# main.net
KiCad netlist of a schematic drawn in Altium Designer
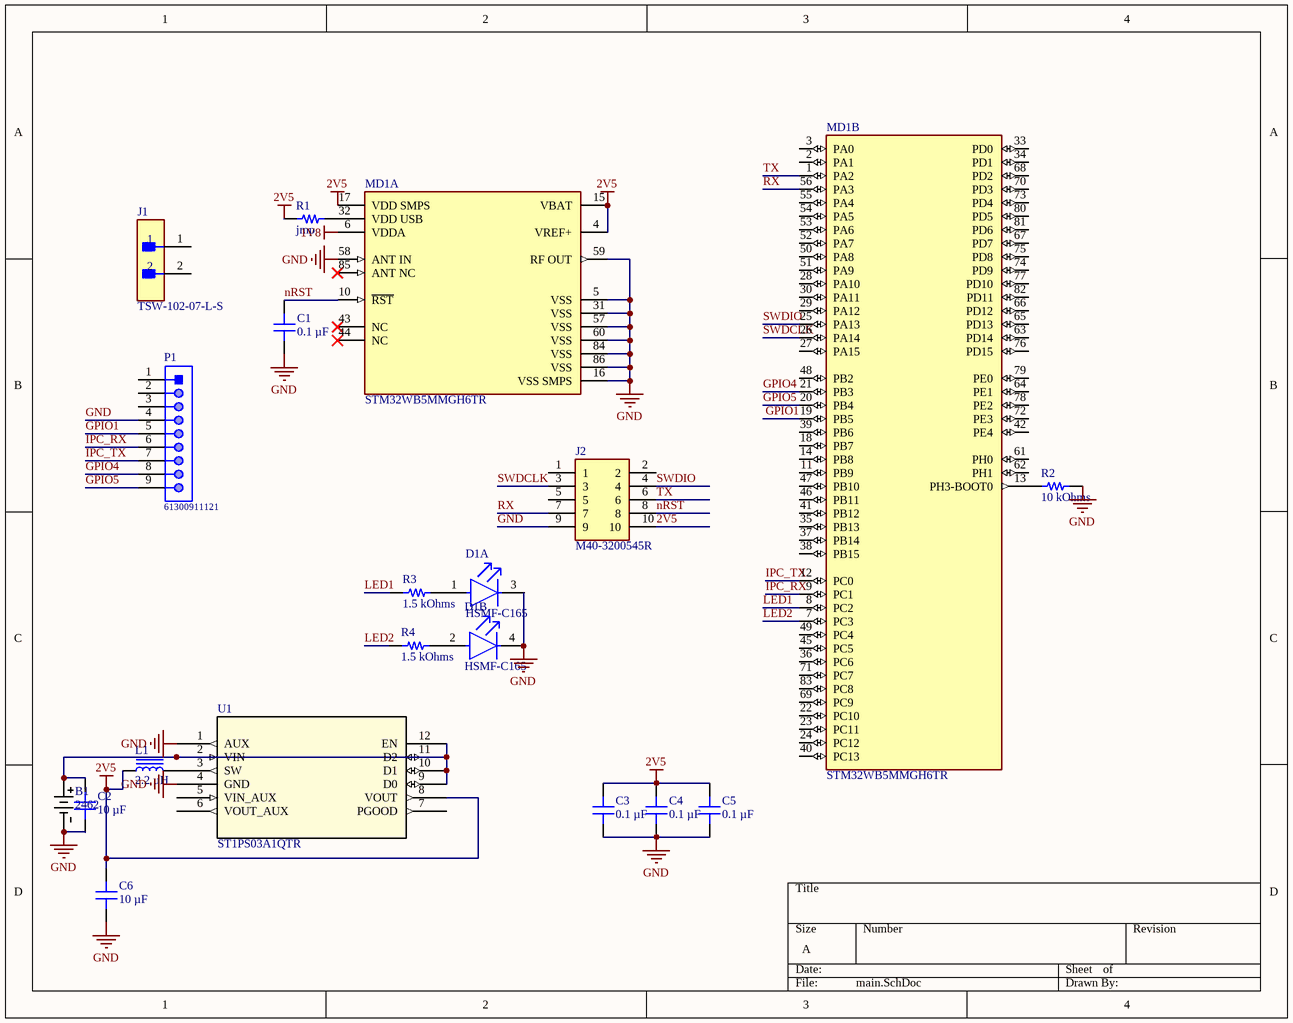
[diagram p0: main.SchDoc]

(export (version "E")
  (design (tool "Eeschema 10.0.6"))
  (components
    (comp (ref "B1")
      (value "2462")
      (footprint "2462_KEY")
      (description "No Description Available")
      (libsource (lib "2462") (part "2462"))
    )
    (comp (ref "C1")
      (value "0.1 µF")
      (footprint "CAP 0402_1005")
      (description "CAP CER 0.1UF 4V X5R 0402")
      (fields (field (name "PART NUMBER") "C0402C104K7PAC7867") (field (name "MANUFACTURER") "KEMET"))
      (libsource (lib "Celestial Altium Library - altium_library") (part "Capacitor"))
    )
    (comp (ref "C2")
      (value "10 µF")
      (footprint "CAP 0603_1608")
      (description "CAP CER 10UF 6.3V X5R 0603")
      (fields
        (field (name "PART NUMBER") "GRM188R60J106ME47D")
        (field (name "MANUFACTURER") "Murata Electronics")
      )
      (libsource (lib "Celestial Altium Library - altium_library") (part "Capacitor"))
    )
    (comp (ref "C3")
      (value "0.1 µF")
      (footprint "CAP 0402_1005")
      (description "CAP CER 0402 0.1UF 16V X7R 10%")
      (fields (field (name "PART NUMBER") "C0402C104K4RECAUTO") (field (name "MANUFACTURER") "KEMET"))
      (libsource (lib "Celestial Altium Library - altium_library") (part "Capacitor"))
    )
    (comp (ref "C4")
      (value "0.1 µF")
      (footprint "CAP 0402_1005")
      (description "CAP CER 0.1UF 4V X5R 0402")
      (fields (field (name "PART NUMBER") "C0402C104K7PAC7867") (field (name "MANUFACTURER") "KEMET"))
      (libsource (lib "Celestial Altium Library - altium_library") (part "Capacitor"))
    )
    (comp (ref "C5")
      (value "0.1 µF")
      (footprint "CAP 0402_1005")
      (description "CAP CER 0.1UF 4V X5R 0402")
      (fields (field (name "PART NUMBER") "C0402C104K7PAC7867") (field (name "MANUFACTURER") "KEMET"))
      (libsource (lib "Celestial Altium Library - altium_library") (part "Capacitor"))
    )
    (comp (ref "C6")
      (value "10 µF")
      (footprint "CAP 0603_1608")
      (description "CAP CER 10UF 6.3V X5R 0603")
      (fields
        (field (name "PART NUMBER") "GRM188R60J106ME47D")
        (field (name "MANUFACTURER") "Murata Electronics")
      )
      (libsource (lib "Celestial Altium Library - altium_library") (part "Capacitor"))
    )
    (comp (ref "D1")
      (value "HSMF-C165")
      (footprint "FP-HSMF-C165-MFG")
      (description "LED GREEN/RED DIFFUSED 0603 SMD")
      (libsource (lib "Altium Content Vault") (part "7c1fe340d8ce6b5db8c50b7ec3493de"))
    )
    (comp (ref "J1")
      (value "TSW-102-07-L-S")
      (footprint "FP-TSW-102-07-L-S-MFG")
      (description "CONN HEADER VERT 2POS 2.54MM")
      (libsource (lib "Altium Content Vault") (part "3bc925449376181038e59eaffc5286c"))
    )
    (comp (ref "J2")
      (value "M40-3200545R")
      (footprint "HARWIN_M40-3200545R")
      (description "Connector Header Surface Mount 10 position 0.039 _1.00mm_")
      (fields (field (name "MF") "Harwin Inc."))
      (libsource (lib "M40-3200545R") (part "M40-3200545R"))
    )
    (comp (ref "L1")
      (value "2.2 µH")
      (footprint "TDK VLS201612CX")
      (description "FIXED IND 6.8UH 930MA 368MOHM SM")
      (fields
        (field (name "PART NUMBER") "VLS201612CX-6R8M-1")
        (field (name "MANUFACTURER") "TDK Corporation")
      )
      (libsource (lib "Celestial Altium Library - altium_library") (part "Inductor"))
    )
    (comp (ref "MD1")
      (value "STM32WB5MMGH6TR")
      (footprint "FP-STM32WB5MMGH6TR-MFG")
      (description "ULTRA-LOW-POWER DUAL CORE ARM CO")
      (libsource (lib "Altium Content Vault") (part "634268d29c17b736a8286639810bf7d"))
    )
    (comp (ref "P1")
      (value "61300911121")
      (footprint "61300911121")
      (description "THT Vertical Pin Header WR-PHD, Pitch 2.54 mm, Single Row, 9 pins")
      (fields (field (name "MANUFACTURER") "Wurth Elektronik") (field (name "PUBLISHER") "WurthElektronik"))
      (libsource (lib "Altium Content Vault") (part "WE-CN-1P-M-R9"))
    )
    (comp (ref "R1")
      (value "jmp")
      (footprint "RES 0402_1005")
      (description "RES 10K OHM 0.1% 1/10W 0402")
      (fields
        (field (name "PART NUMBER") "RP73PF1E10KBTD")
        (field (name "MANUFACTURER") "TE Connectivity Passive Product")
      )
      (libsource (lib "Celestial Altium Library - altium_library") (part "Resistor"))
    )
    (comp (ref "R2")
      (value "10 kOhms")
      (footprint "RES 0402_1005")
      (description "RES 10K OHM 0.1% 1/10W 0402")
      (fields
        (field (name "PART NUMBER") "RP73PF1E10KBTD")
        (field (name "MANUFACTURER") "TE Connectivity Passive Product")
      )
      (libsource (lib "Celestial Altium Library - altium_library") (part "Resistor"))
    )
    (comp (ref "R3")
      (value "1.5 kOhms")
      (footprint "RES 0402_1005")
      (description "RES 1.5K OHM 0.05% 1/10W 0402")
      (fields
        (field (name "PART NUMBER") "ERA-2VRW1501X")
        (field (name "MANUFACTURER") "Panasonic Electronic Components")
      )
      (libsource (lib "Celestial Altium Library - altium_library") (part "Resistor"))
    )
    (comp (ref "R4")
      (value "1.5 kOhms")
      (footprint "RES 0402_1005")
      (description "RES 1.5K OHM 0.05% 1/10W 0402")
      (fields
        (field (name "PART NUMBER") "ERA-2VRW1501X")
        (field (name "MANUFACTURER") "Panasonic Electronic Components")
      )
      (libsource (lib "Celestial Altium Library - altium_library") (part "Resistor"))
    )
    (comp (ref "U1")
      (value "ST1PS03A1QTR")
      (footprint "TQFN12_2X1P7_STM")
      (description "No Description Available")
      (libsource (lib "ST1PS03A1QTR") (part "ST1PS03A1QTR"))
    )
  )
  (nets
    (net (code "1") (name "/GPIO1") (class "Default")
      (node (ref "MD1") (pin "19") (pinfunction "PB5_19") (pintype "bidirectional"))
      (node (ref "P1") (pin "5") (pinfunction "5_5") (pintype "passive"))
    )
    (net (code "2") (name "/GPIO4") (class "Default")
      (node (ref "MD1") (pin "21") (pinfunction "PB3_21") (pintype "bidirectional"))
      (node (ref "P1") (pin "8") (pinfunction "8_8") (pintype "passive"))
    )
    (net (code "3") (name "/GPIO5") (class "Default")
      (node (ref "MD1") (pin "20") (pinfunction "PB4_20") (pintype "bidirectional"))
      (node (ref "P1") (pin "9") (pinfunction "9_9") (pintype "passive"))
    )
    (net (code "4") (name "/IPC_RX") (class "Default")
      (node (ref "MD1") (pin "9") (pinfunction "PC1_9") (pintype "bidirectional"))
      (node (ref "P1") (pin "6") (pinfunction "6_6") (pintype "passive"))
    )
    (net (code "5") (name "/IPC_TX") (class "Default")
      (node (ref "MD1") (pin "12") (pinfunction "PC0_12") (pintype "bidirectional"))
      (node (ref "P1") (pin "7") (pinfunction "7_7") (pintype "passive"))
    )
    (net (code "6") (name "/LED1") (class "Default")
      (node (ref "MD1") (pin "8") (pinfunction "PC2_8") (pintype "bidirectional"))
      (node (ref "R3") (pin "2") (pinfunction "2_2") (pintype "passive"))
    )
    (net (code "7") (name "/LED2") (class "Default")
      (node (ref "MD1") (pin "7") (pinfunction "PC3_7") (pintype "bidirectional"))
      (node (ref "R4") (pin "2") (pinfunction "2_2") (pintype "passive"))
    )
    (net (code "8") (name "/RX") (class "Default")
      (node (ref "J2") (pin "7") (pinfunction "7_7") (pintype "passive"))
      (node (ref "MD1") (pin "56") (pinfunction "PA3_56") (pintype "bidirectional"))
    )
    (net (code "9") (name "/SWDCLK") (class "Default")
      (node (ref "J2") (pin "3") (pinfunction "3_3") (pintype "passive"))
      (node (ref "MD1") (pin "26") (pinfunction "PA14_26") (pintype "bidirectional"))
    )
    (net (code "10") (name "/SWDIO") (class "Default")
      (node (ref "J2") (pin "4") (pinfunction "4_4") (pintype "passive"))
      (node (ref "MD1") (pin "25") (pinfunction "PA13_25") (pintype "bidirectional"))
    )
    (net (code "11") (name "/TX") (class "Default")
      (node (ref "J2") (pin "6") (pinfunction "6_6") (pintype "passive"))
      (node (ref "MD1") (pin "1") (pinfunction "PA2_1") (pintype "bidirectional"))
    )
    (net (code "12") (name "/nRST") (class "Default")
      (node (ref "C1") (pin "1") (pinfunction "1_1") (pintype "passive"))
      (node (ref "J2") (pin "8") (pinfunction "8_8") (pintype "passive"))
      (node (ref "MD1") (pin "10") (pinfunction "~{RST}_10") (pintype "input"))
    )
    (net (code "13") (name "1V8") (class "Default")
      (node (ref "MD1") (pin "6") (pinfunction "VDDA_6") (pintype "power_in"))
    )
    (net (code "14") (name "2V5") (class "Default")
      (node (ref "C3") (pin "2") (pinfunction "2_2") (pintype "passive"))
      (node (ref "C4") (pin "2") (pinfunction "2_2") (pintype "passive"))
      (node (ref "C5") (pin "2") (pinfunction "2_2") (pintype "passive"))
      (node (ref "C6") (pin "2") (pinfunction "2_2") (pintype "passive"))
      (node (ref "J2") (pin "10") (pinfunction "10_10") (pintype "passive"))
      (node (ref "L1") (pin "1") (pinfunction "1_1") (pintype "passive"))
      (node (ref "MD1") (pin "15") (pinfunction "VBAT_15") (pintype "power_in"))
      (node (ref "MD1") (pin "17") (pinfunction "VDD_SMPS_17") (pintype "power_in"))
      (node (ref "MD1") (pin "4") (pinfunction "VREF+_4") (pintype "power_in"))
      (node (ref "R1") (pin "1") (pinfunction "1_1") (pintype "passive"))
      (node (ref "U1") (pin "8") (pinfunction "VOUT_8") (pintype "output"))
    )
    (net (code "15") (name "GND") (class "Default")
      (node (ref "B1") (pin "1") (pinfunction "1_1") (pintype "passive"))
      (node (ref "C1") (pin "2") (pinfunction "2_2") (pintype "passive"))
      (node (ref "C2") (pin "1") (pinfunction "1_1") (pintype "passive"))
      (node (ref "C3") (pin "1") (pinfunction "1_1") (pintype "passive"))
      (node (ref "C4") (pin "1") (pinfunction "1_1") (pintype "passive"))
      (node (ref "C5") (pin "1") (pinfunction "1_1") (pintype "passive"))
      (node (ref "C6") (pin "1") (pinfunction "1_1") (pintype "passive"))
      (node (ref "D1") (pin "4") (pinfunction "RED_C_4") (pintype "passive"))
      (node (ref "J2") (pin "9") (pinfunction "9_9") (pintype "passive"))
      (node (ref "MD1") (pin "16") (pinfunction "VSS_SMPS_16") (pintype "power_in"))
      (node (ref "MD1") (pin "31") (pinfunction "VSS_31") (pintype "power_in"))
      (node (ref "MD1") (pin "5") (pinfunction "VSS_5") (pintype "power_in"))
      (node (ref "MD1") (pin "57") (pinfunction "VSS_57") (pintype "power_in"))
      (node (ref "MD1") (pin "58") (pinfunction "ANT_IN_58") (pintype "input"))
      (node (ref "MD1") (pin "59") (pinfunction "RF_OUT_59") (pintype "output"))
      (node (ref "MD1") (pin "60") (pinfunction "VSS_60") (pintype "power_in"))
      (node (ref "MD1") (pin "84") (pinfunction "VSS_84") (pintype "power_in"))
      (node (ref "MD1") (pin "86") (pinfunction "VSS_86") (pintype "power_in"))
      (node (ref "P1") (pin "4") (pinfunction "4_4") (pintype "passive"))
      (node (ref "R2") (pin "1") (pinfunction "1_1") (pintype "passive"))
      (node (ref "U1") (pin "1") (pinfunction "AUX_1") (pintype "output"))
      (node (ref "U1") (pin "4") (pinfunction "GND_4") (pintype "power_in"))
    )
    (net (code "16") (name "Net-(D1A-GREEN_A)") (class "Default")
      (node (ref "D1") (pin "1") (pinfunction "GREEN_A_1") (pintype "passive"))
      (node (ref "R3") (pin "1") (pinfunction "1_1") (pintype "passive"))
    )
    (net (code "17") (name "Net-(D1B-RED_A)") (class "Default")
      (node (ref "D1") (pin "2") (pinfunction "RED_A_2") (pintype "passive"))
      (node (ref "R4") (pin "1") (pinfunction "1_1") (pintype "passive"))
    )
    (net (code "18") (name "Net-(MD1A-VDD_USB)") (class "Default")
      (node (ref "MD1") (pin "32") (pinfunction "VDD_USB_32") (pintype "power_in"))
      (node (ref "R1") (pin "2") (pinfunction "2_2") (pintype "passive"))
    )
    (net (code "19") (name "Net-(MD1B-PH3-BOOT0)") (class "Default")
      (node (ref "MD1") (pin "13") (pinfunction "PH3-BOOT0_13") (pintype "output"))
      (node (ref "R2") (pin "2") (pinfunction "2_2") (pintype "passive"))
    )
    (net (code "20") (name "Net-(U1-D0)") (class "Default")
      (node (ref "B1") (pin "2") (pinfunction "2_2") (pintype "passive"))
      (node (ref "C2") (pin "2") (pinfunction "2_2") (pintype "passive"))
      (node (ref "U1") (pin "10") (pinfunction "D1_10") (pintype "bidirectional"))
      (node (ref "U1") (pin "11") (pinfunction "D2_11") (pintype "bidirectional"))
      (node (ref "U1") (pin "12") (pinfunction "EN_12") (pintype "passive"))
      (node (ref "U1") (pin "2") (pinfunction "VIN_2") (pintype "input"))
      (node (ref "U1") (pin "9") (pinfunction "D0_9") (pintype "bidirectional"))
    )
    (net (code "21") (name "Net-(U1-SW)") (class "Default")
      (node (ref "L1") (pin "2") (pinfunction "2_2") (pintype "passive"))
      (node (ref "U1") (pin "3") (pinfunction "SW_3") (pintype "output"))
    )
    (net (code "22") (name "unconnected-(D1A-GREEN_C-Pad3)") (class "Default")
      (node (ref "D1") (pin "3") (pinfunction "GREEN_C_3") (pintype "passive"))
    )
    (net (code "23") (name "unconnected-(J1-Pad1)") (class "Default")
      (node (ref "J1") (pin "1") (pinfunction "1_1") (pintype "passive"))
    )
    (net (code "24") (name "unconnected-(J1-Pad2)") (class "Default")
      (node (ref "J1") (pin "2") (pinfunction "2_2") (pintype "passive"))
    )
    (net (code "25") (name "unconnected-(J2-Pad1)") (class "Default")
      (node (ref "J2") (pin "1") (pinfunction "1_1") (pintype "passive"))
    )
    (net (code "26") (name "unconnected-(J2-Pad2)") (class "Default")
      (node (ref "J2") (pin "2") (pinfunction "2_2") (pintype "passive"))
    )
    (net (code "27") (name "unconnected-(J2-Pad5)") (class "Default")
      (node (ref "J2") (pin "5") (pinfunction "5_5") (pintype "passive"))
    )
    (net (code "28") (name "unconnected-(MD1A-ANT_NC-Pad85)") (class "Default")
      (node (ref "MD1") (pin "85") (pinfunction "ANT_NC_85") (pintype "input+no_connect"))
    )
    (net (code "29") (name "unconnected-(MD1A-NC-Pad43)") (class "Default")
      (node (ref "MD1") (pin "43") (pinfunction "NC_43") (pintype "passive+no_connect"))
    )
    (net (code "30") (name "unconnected-(MD1A-NC-Pad44)") (class "Default")
      (node (ref "MD1") (pin "44") (pinfunction "NC_44") (pintype "passive+no_connect"))
    )
    (net (code "31") (name "unconnected-(MD1B-PA0-Pad3)") (class "Default")
      (node (ref "MD1") (pin "3") (pinfunction "PA0_3") (pintype "bidirectional"))
    )
    (net (code "32") (name "unconnected-(MD1B-PA1-Pad2)") (class "Default")
      (node (ref "MD1") (pin "2") (pinfunction "PA1_2") (pintype "bidirectional"))
    )
    (net (code "33") (name "unconnected-(MD1B-PA4-Pad55)") (class "Default")
      (node (ref "MD1") (pin "55") (pinfunction "PA4_55") (pintype "bidirectional"))
    )
    (net (code "34") (name "unconnected-(MD1B-PA5-Pad54)") (class "Default")
      (node (ref "MD1") (pin "54") (pinfunction "PA5_54") (pintype "bidirectional"))
    )
    (net (code "35") (name "unconnected-(MD1B-PA6-Pad53)") (class "Default")
      (node (ref "MD1") (pin "53") (pinfunction "PA6_53") (pintype "bidirectional"))
    )
    (net (code "36") (name "unconnected-(MD1B-PA7-Pad52)") (class "Default")
      (node (ref "MD1") (pin "52") (pinfunction "PA7_52") (pintype "bidirectional"))
    )
    (net (code "37") (name "unconnected-(MD1B-PA8-Pad50)") (class "Default")
      (node (ref "MD1") (pin "50") (pinfunction "PA8_50") (pintype "bidirectional"))
    )
    (net (code "38") (name "unconnected-(MD1B-PA9-Pad51)") (class "Default")
      (node (ref "MD1") (pin "51") (pinfunction "PA9_51") (pintype "bidirectional"))
    )
    (net (code "39") (name "unconnected-(MD1B-PA10-Pad28)") (class "Default")
      (node (ref "MD1") (pin "28") (pinfunction "PA10_28") (pintype "bidirectional"))
    )
    (net (code "40") (name "unconnected-(MD1B-PA11-Pad30)") (class "Default")
      (node (ref "MD1") (pin "30") (pinfunction "PA11_30") (pintype "bidirectional"))
    )
    (net (code "41") (name "unconnected-(MD1B-PA12-Pad29)") (class "Default")
      (node (ref "MD1") (pin "29") (pinfunction "PA12_29") (pintype "bidirectional"))
    )
    (net (code "42") (name "unconnected-(MD1B-PA15-Pad27)") (class "Default")
      (node (ref "MD1") (pin "27") (pinfunction "PA15_27") (pintype "bidirectional"))
    )
    (net (code "43") (name "unconnected-(MD1B-PB2-Pad48)") (class "Default")
      (node (ref "MD1") (pin "48") (pinfunction "PB2_48") (pintype "bidirectional"))
    )
    (net (code "44") (name "unconnected-(MD1B-PB6-Pad39)") (class "Default")
      (node (ref "MD1") (pin "39") (pinfunction "PB6_39") (pintype "bidirectional"))
    )
    (net (code "45") (name "unconnected-(MD1B-PB7-Pad18)") (class "Default")
      (node (ref "MD1") (pin "18") (pinfunction "PB7_18") (pintype "bidirectional"))
    )
    (net (code "46") (name "unconnected-(MD1B-PB8-Pad14)") (class "Default")
      (node (ref "MD1") (pin "14") (pinfunction "PB8_14") (pintype "bidirectional"))
    )
    (net (code "47") (name "unconnected-(MD1B-PB9-Pad11)") (class "Default")
      (node (ref "MD1") (pin "11") (pinfunction "PB9_11") (pintype "bidirectional"))
    )
    (net (code "48") (name "unconnected-(MD1B-PB10-Pad47)") (class "Default")
      (node (ref "MD1") (pin "47") (pinfunction "PB10_47") (pintype "bidirectional"))
    )
    (net (code "49") (name "unconnected-(MD1B-PB11-Pad46)") (class "Default")
      (node (ref "MD1") (pin "46") (pinfunction "PB11_46") (pintype "bidirectional"))
    )
    (net (code "50") (name "unconnected-(MD1B-PB12-Pad41)") (class "Default")
      (node (ref "MD1") (pin "41") (pinfunction "PB12_41") (pintype "bidirectional"))
    )
    (net (code "51") (name "unconnected-(MD1B-PB13-Pad35)") (class "Default")
      (node (ref "MD1") (pin "35") (pinfunction "PB13_35") (pintype "bidirectional"))
    )
    (net (code "52") (name "unconnected-(MD1B-PB14-Pad37)") (class "Default")
      (node (ref "MD1") (pin "37") (pinfunction "PB14_37") (pintype "bidirectional"))
    )
    (net (code "53") (name "unconnected-(MD1B-PB15-Pad38)") (class "Default")
      (node (ref "MD1") (pin "38") (pinfunction "PB15_38") (pintype "bidirectional"))
    )
    (net (code "54") (name "unconnected-(MD1B-PC4-Pad49)") (class "Default")
      (node (ref "MD1") (pin "49") (pinfunction "PC4_49") (pintype "bidirectional"))
    )
    (net (code "55") (name "unconnected-(MD1B-PC5-Pad45)") (class "Default")
      (node (ref "MD1") (pin "45") (pinfunction "PC5_45") (pintype "bidirectional"))
    )
    (net (code "56") (name "unconnected-(MD1B-PC6-Pad36)") (class "Default")
      (node (ref "MD1") (pin "36") (pinfunction "PC6_36") (pintype "bidirectional"))
    )
    (net (code "57") (name "unconnected-(MD1B-PC7-Pad71)") (class "Default")
      (node (ref "MD1") (pin "71") (pinfunction "PC7_71") (pintype "bidirectional"))
    )
    (net (code "58") (name "unconnected-(MD1B-PC8-Pad83)") (class "Default")
      (node (ref "MD1") (pin "83") (pinfunction "PC8_83") (pintype "bidirectional"))
    )
    (net (code "59") (name "unconnected-(MD1B-PC9-Pad69)") (class "Default")
      (node (ref "MD1") (pin "69") (pinfunction "PC9_69") (pintype "bidirectional"))
    )
    (net (code "60") (name "unconnected-(MD1B-PC10-Pad22)") (class "Default")
      (node (ref "MD1") (pin "22") (pinfunction "PC10_22") (pintype "bidirectional"))
    )
    (net (code "61") (name "unconnected-(MD1B-PC11-Pad23)") (class "Default")
      (node (ref "MD1") (pin "23") (pinfunction "PC11_23") (pintype "bidirectional"))
    )
    (net (code "62") (name "unconnected-(MD1B-PC12-Pad24)") (class "Default")
      (node (ref "MD1") (pin "24") (pinfunction "PC12_24") (pintype "bidirectional"))
    )
    (net (code "63") (name "unconnected-(MD1B-PC13-Pad40)") (class "Default")
      (node (ref "MD1") (pin "40") (pinfunction "PC13_40") (pintype "bidirectional"))
    )
    (net (code "64") (name "unconnected-(MD1B-PD0-Pad33)") (class "Default")
      (node (ref "MD1") (pin "33") (pinfunction "PD0_33") (pintype "bidirectional"))
    )
    (net (code "65") (name "unconnected-(MD1B-PD1-Pad34)") (class "Default")
      (node (ref "MD1") (pin "34") (pinfunction "PD1_34") (pintype "bidirectional"))
    )
    (net (code "66") (name "unconnected-(MD1B-PD2-Pad68)") (class "Default")
      (node (ref "MD1") (pin "68") (pinfunction "PD2_68") (pintype "bidirectional"))
    )
    (net (code "67") (name "unconnected-(MD1B-PD3-Pad70)") (class "Default")
      (node (ref "MD1") (pin "70") (pinfunction "PD3_70") (pintype "bidirectional"))
    )
    (net (code "68") (name "unconnected-(MD1B-PD4-Pad73)") (class "Default")
      (node (ref "MD1") (pin "73") (pinfunction "PD4_73") (pintype "bidirectional"))
    )
    (net (code "69") (name "unconnected-(MD1B-PD5-Pad80)") (class "Default")
      (node (ref "MD1") (pin "80") (pinfunction "PD5_80") (pintype "bidirectional"))
    )
    (net (code "70") (name "unconnected-(MD1B-PD6-Pad81)") (class "Default")
      (node (ref "MD1") (pin "81") (pinfunction "PD6_81") (pintype "bidirectional"))
    )
    (net (code "71") (name "unconnected-(MD1B-PD7-Pad67)") (class "Default")
      (node (ref "MD1") (pin "67") (pinfunction "PD7_67") (pintype "bidirectional"))
    )
    (net (code "72") (name "unconnected-(MD1B-PD8-Pad75)") (class "Default")
      (node (ref "MD1") (pin "75") (pinfunction "PD8_75") (pintype "bidirectional"))
    )
    (net (code "73") (name "unconnected-(MD1B-PD9-Pad74)") (class "Default")
      (node (ref "MD1") (pin "74") (pinfunction "PD9_74") (pintype "bidirectional"))
    )
    (net (code "74") (name "unconnected-(MD1B-PD10-Pad77)") (class "Default")
      (node (ref "MD1") (pin "77") (pinfunction "PD10_77") (pintype "bidirectional"))
    )
    (net (code "75") (name "unconnected-(MD1B-PD11-Pad82)") (class "Default")
      (node (ref "MD1") (pin "82") (pinfunction "PD11_82") (pintype "bidirectional"))
    )
    (net (code "76") (name "unconnected-(MD1B-PD12-Pad66)") (class "Default")
      (node (ref "MD1") (pin "66") (pinfunction "PD12_66") (pintype "bidirectional"))
    )
    (net (code "77") (name "unconnected-(MD1B-PD13-Pad65)") (class "Default")
      (node (ref "MD1") (pin "65") (pinfunction "PD13_65") (pintype "bidirectional"))
    )
    (net (code "78") (name "unconnected-(MD1B-PD14-Pad63)") (class "Default")
      (node (ref "MD1") (pin "63") (pinfunction "PD14_63") (pintype "bidirectional"))
    )
    (net (code "79") (name "unconnected-(MD1B-PD15-Pad76)") (class "Default")
      (node (ref "MD1") (pin "76") (pinfunction "PD15_76") (pintype "bidirectional"))
    )
    (net (code "80") (name "unconnected-(MD1B-PE0-Pad79)") (class "Default")
      (node (ref "MD1") (pin "79") (pinfunction "PE0_79") (pintype "bidirectional"))
    )
    (net (code "81") (name "unconnected-(MD1B-PE1-Pad64)") (class "Default")
      (node (ref "MD1") (pin "64") (pinfunction "PE1_64") (pintype "bidirectional"))
    )
    (net (code "82") (name "unconnected-(MD1B-PE2-Pad78)") (class "Default")
      (node (ref "MD1") (pin "78") (pinfunction "PE2_78") (pintype "bidirectional"))
    )
    (net (code "83") (name "unconnected-(MD1B-PE3-Pad72)") (class "Default")
      (node (ref "MD1") (pin "72") (pinfunction "PE3_72") (pintype "bidirectional"))
    )
    (net (code "84") (name "unconnected-(MD1B-PE4-Pad42)") (class "Default")
      (node (ref "MD1") (pin "42") (pinfunction "PE4_42") (pintype "bidirectional"))
    )
    (net (code "85") (name "unconnected-(MD1B-PH0-Pad61)") (class "Default")
      (node (ref "MD1") (pin "61") (pinfunction "PH0_61") (pintype "bidirectional"))
    )
    (net (code "86") (name "unconnected-(MD1B-PH1-Pad62)") (class "Default")
      (node (ref "MD1") (pin "62") (pinfunction "PH1_62") (pintype "bidirectional"))
    )
    (net (code "87") (name "unconnected-(P1-Pad1)") (class "Default")
      (node (ref "P1") (pin "1") (pinfunction "1_1") (pintype "passive"))
    )
    (net (code "88") (name "unconnected-(P1-Pad2)") (class "Default")
      (node (ref "P1") (pin "2") (pinfunction "2_2") (pintype "passive"))
    )
    (net (code "89") (name "unconnected-(P1-Pad3)") (class "Default")
      (node (ref "P1") (pin "3") (pinfunction "3_3") (pintype "passive"))
    )
    (net (code "90") (name "unconnected-(U1-PGOOD-Pad7)") (class "Default")
      (node (ref "U1") (pin "7") (pinfunction "PGOOD_7") (pintype "output"))
    )
    (net (code "91") (name "unconnected-(U1-VIN_AUX-Pad5)") (class "Default")
      (node (ref "U1") (pin "5") (pinfunction "VIN_AUX_5") (pintype "input"))
    )
    (net (code "92") (name "unconnected-(U1-VOUT_AUX-Pad6)") (class "Default")
      (node (ref "U1") (pin "6") (pinfunction "VOUT_AUX_6") (pintype "output"))
    )
  )
)
